# Gyroscope-Acceleromter.net
KiCad netlist of a schematic drawn in Altium Designer
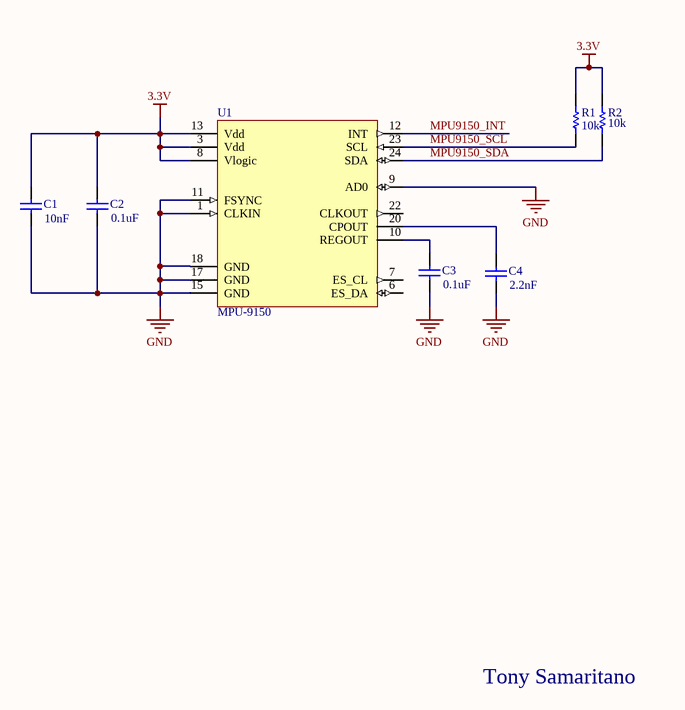
[diagram p0: Gyroscope-Acceleromter.SchDoc]

(export (version "E")
  (design (tool "Eeschema 10.0.6"))
  (components
    (comp (ref "C1")
      (value "10nF")
      (footprint "1608[0603]")
      (description "Capacitor (Semiconductor SIM Model)")
      (fields (field (name "Comment") "Cap Semi") (field (name "PUBLISHER") "Altium Limited"))
      (libsource (lib "Miscellaneous Devices") (part "Cap Semi"))
    )
    (comp (ref "C2")
      (value "0.1uF")
      (footprint "1608[0603]")
      (description "Capacitor (Semiconductor SIM Model)")
      (fields (field (name "Comment") "Cap Semi") (field (name "PUBLISHER") "Altium Limited"))
      (libsource (lib "Miscellaneous Devices") (part "Cap Semi"))
    )
    (comp (ref "C3")
      (value "0.1uF")
      (footprint "1608[0603]")
      (description "Capacitor (Semiconductor SIM Model)")
      (fields (field (name "Comment") "Cap Semi") (field (name "PUBLISHER") "Altium Limited"))
      (libsource (lib "Miscellaneous Devices") (part "Cap Semi"))
    )
    (comp (ref "C4")
      (value "2.2nF")
      (footprint "1608[0603]")
      (description "Capacitor (Semiconductor SIM Model)")
      (fields (field (name "Comment") "Cap Semi") (field (name "PUBLISHER") "Altium Limited"))
      (libsource (lib "Miscellaneous Devices") (part "Cap Semi"))
    )
    (comp (ref "R1")
      (value "10k")
      (footprint "0603")
      (description "Resistor")
      (fields (field (name "PUBLISHER") "Altium Limited"))
      (libsource (lib "passives") (part "Resistor"))
    )
    (comp (ref "R2")
      (value "10k")
      (footprint "0603")
      (description "Resistor")
      (fields (field (name "PUBLISHER") "Altium Limited"))
      (libsource (lib "passives") (part "Resistor"))
    )
    (comp (ref "U1") (value "MPU-9150") (footprint "MPU-9150") (libsource (lib "Devices") (part "MPU-9150")))
  )
  (nets
    (net (code "1") (name "/MPU9150_INT") (class "Default")
      (node (ref "U1") (pin "12") (pinfunction "INT_12") (pintype "output"))
    )
    (net (code "2") (name "/MPU9150_SCL") (class "Default")
      (node (ref "R1") (pin "1") (pinfunction "1_1") (pintype "passive"))
      (node (ref "U1") (pin "23") (pinfunction "SCL_23") (pintype "input"))
    )
    (net (code "3") (name "/MPU9150_SDA") (class "Default")
      (node (ref "R2") (pin "1") (pinfunction "1_1") (pintype "passive"))
      (node (ref "U1") (pin "24") (pinfunction "SDA_24") (pintype "bidirectional"))
    )
    (net (code "4") (name "3.3V") (class "Default")
      (node (ref "C1") (pin "2") (pinfunction "2_2") (pintype "passive"))
      (node (ref "C2") (pin "2") (pinfunction "2_2") (pintype "passive"))
      (node (ref "R1") (pin "2") (pinfunction "2_2") (pintype "passive"))
      (node (ref "R2") (pin "2") (pinfunction "2_2") (pintype "passive"))
      (node (ref "U1") (pin "13") (pinfunction "Vdd_13") (pintype "passive"))
      (node (ref "U1") (pin "3") (pinfunction "Vdd_3") (pintype "passive"))
      (node (ref "U1") (pin "8") (pinfunction "Vlogic_8") (pintype "passive"))
    )
    (net (code "5") (name "GND") (class "Default")
      (node (ref "C1") (pin "1") (pinfunction "1_1") (pintype "passive"))
      (node (ref "C2") (pin "1") (pinfunction "1_1") (pintype "passive"))
      (node (ref "C3") (pin "1") (pinfunction "1_1") (pintype "passive"))
      (node (ref "C4") (pin "1") (pinfunction "1_1") (pintype "passive"))
      (node (ref "U1") (pin "1") (pinfunction "CLKIN_1") (pintype "input"))
      (node (ref "U1") (pin "11") (pinfunction "FSYNC_11") (pintype "input"))
      (node (ref "U1") (pin "15") (pinfunction "GND_15") (pintype "passive"))
      (node (ref "U1") (pin "17") (pinfunction "GND_17") (pintype "passive"))
      (node (ref "U1") (pin "18") (pinfunction "GND_18") (pintype "passive"))
      (node (ref "U1") (pin "9") (pinfunction "AD0_9") (pintype "bidirectional"))
    )
    (net (code "6") (name "Net-(U1-CPOUT)") (class "Default")
      (node (ref "C4") (pin "2") (pinfunction "2_2") (pintype "passive"))
      (node (ref "U1") (pin "20") (pinfunction "CPOUT_20") (pintype "passive"))
    )
    (net (code "7") (name "Net-(U1-REGOUT)") (class "Default")
      (node (ref "C3") (pin "2") (pinfunction "2_2") (pintype "passive"))
      (node (ref "U1") (pin "10") (pinfunction "REGOUT_10") (pintype "passive"))
    )
    (net (code "8") (name "unconnected-(U1-CLKOUT-Pad22)") (class "Default")
      (node (ref "U1") (pin "22") (pinfunction "CLKOUT_22") (pintype "output"))
    )
    (net (code "9") (name "unconnected-(U1-ES_CL-Pad7)") (class "Default")
      (node (ref "U1") (pin "7") (pinfunction "ES_CL_7") (pintype "output"))
    )
    (net (code "10") (name "unconnected-(U1-ES_DA-Pad6)") (class "Default")
      (node (ref "U1") (pin "6") (pinfunction "ES_DA_6") (pintype "bidirectional"))
    )
  )
)
